# FSPad_sch.net
KiCad netlist of a schematic drawn in EAGLE
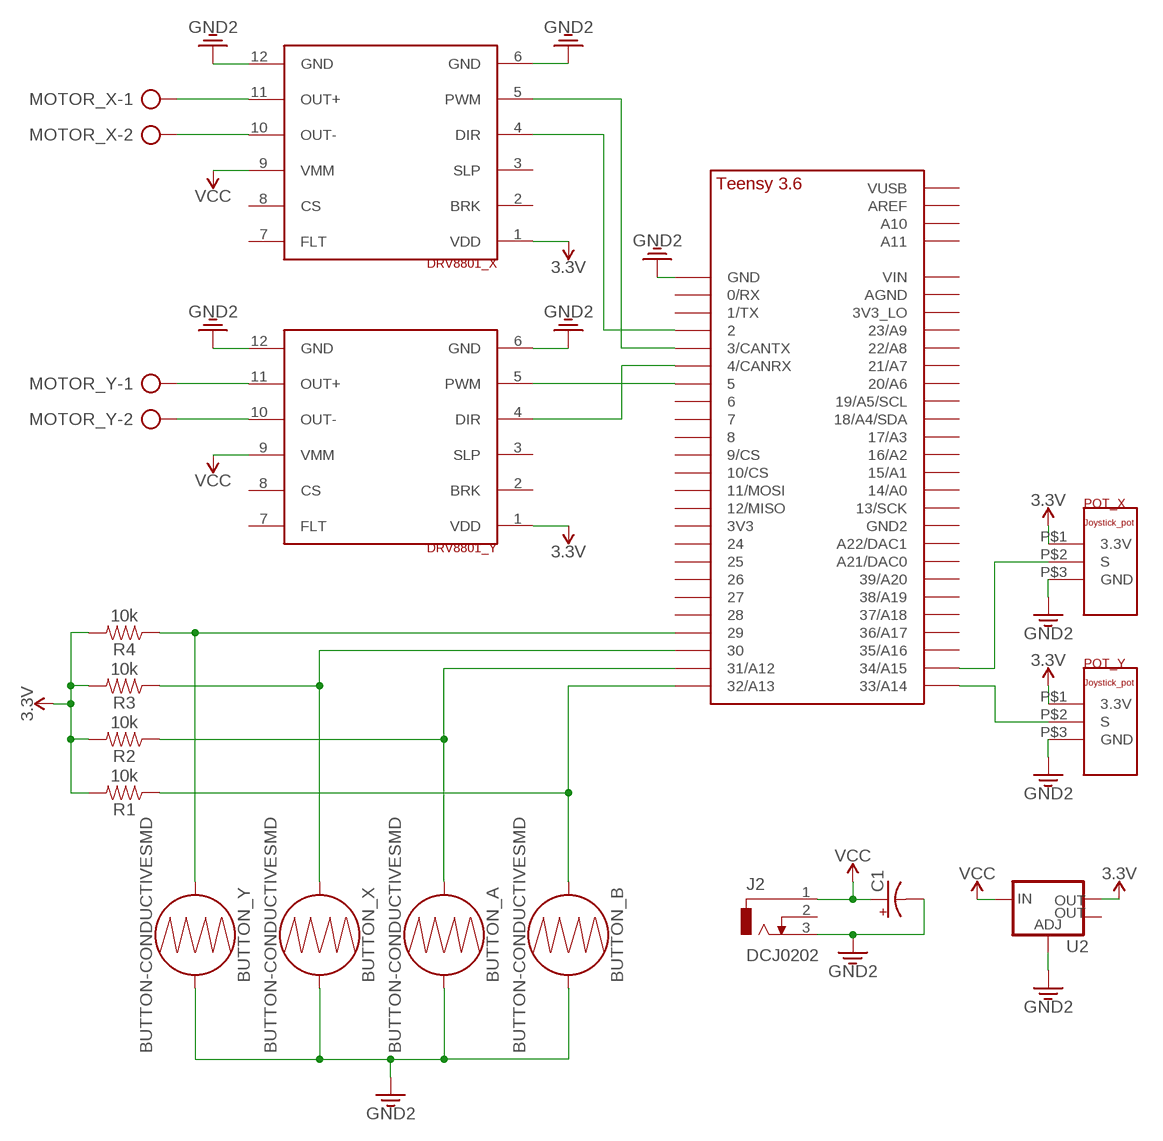
[diagram p0: schematic, sheet 1]

(export (version "E")
  (design (tool "Eeschema 10.0.6"))
  (components
    (comp (ref "BUTTON_A")
      (value "BUTTON-CONDUCTIVESMD")
      (footprint "eagle-import:BUTTON-CONDUCTIVE")
      (libsource (lib "eagle-import") (part "BUTTON-CONDUCTIVESMD"))
    )
    (comp (ref "BUTTON_B")
      (value "BUTTON-CONDUCTIVESMD")
      (footprint "eagle-import:BUTTON-CONDUCTIVE")
      (libsource (lib "eagle-import") (part "BUTTON-CONDUCTIVESMD"))
    )
    (comp (ref "BUTTON_X")
      (value "BUTTON-CONDUCTIVESMD")
      (footprint "eagle-import:BUTTON-CONDUCTIVE")
      (libsource (lib "eagle-import") (part "BUTTON-CONDUCTIVESMD"))
    )
    (comp (ref "BUTTON_Y")
      (value "BUTTON-CONDUCTIVESMD")
      (footprint "eagle-import:BUTTON-CONDUCTIVE")
      (libsource (lib "eagle-import") (part "BUTTON-CONDUCTIVESMD"))
    )
    (comp (ref "C1")
      (value "1mF")
      (footprint "eagle-import:CPOL-RADIAL-5MM-10MM")
      (libsource (lib "eagle-import") (part "1000UF-RADIAL-5MM-25V-20%"))
    )
    (comp (ref "DRV8801_X")
      (value "DRV8801_BREAKOUT_BOARD")
      (footprint "eagle-import:DRV8801_BREAKOUT_BOARD")
      (libsource (lib "eagle-import") (part "DRV8801_BREAKOUT_BOARD"))
    )
    (comp (ref "DRV8801_Y")
      (value "DRV8801_BREAKOUT_BOARD")
      (footprint "eagle-import:DRV8801_BREAKOUT_BOARD")
      (libsource (lib "eagle-import") (part "DRV8801_BREAKOUT_BOARD"))
    )
    (comp (ref "J2")
      (value "DCJ0202")
      (footprint "eagle-import:DCJ0202")
      (libsource (lib "eagle-import") (part "DCJ0202"))
    )
    (comp (ref "MOTOR_X")
      (value "AK300/2")
      (footprint "eagle-import:AK300_2")
      (libsource (lib "eagle-import") (part "AK300/2"))
    )
    (comp (ref "MOTOR_Y")
      (value "AK300/2")
      (footprint "eagle-import:AK300_2")
      (libsource (lib "eagle-import") (part "AK300/2"))
    )
    (comp (ref "POT_X")
      (value "JOYSTICK_POT")
      (footprint "eagle-import:JOYSTICK_POT")
      (libsource (lib "eagle-import") (part "JOYSTICK_POT"))
    )
    (comp (ref "POT_Y")
      (value "JOYSTICK_POT")
      (footprint "eagle-import:JOYSTICK_POT")
      (libsource (lib "eagle-import") (part "JOYSTICK_POT"))
    )
    (comp (ref "R1")
      (value "10k")
      (footprint "eagle-import:AXIAL-0.3")
      (libsource (lib "eagle-import") (part "10KOHM-HORIZ-1/4W-1%"))
    )
    (comp (ref "R2")
      (value "10k")
      (footprint "eagle-import:AXIAL-0.3")
      (libsource (lib "eagle-import") (part "10KOHM-HORIZ-1/4W-1%"))
    )
    (comp (ref "R3")
      (value "10k")
      (footprint "eagle-import:AXIAL-0.3")
      (libsource (lib "eagle-import") (part "10KOHM-HORIZ-1/4W-1%"))
    )
    (comp (ref "R4")
      (value "10k")
      (footprint "eagle-import:AXIAL-0.3")
      (libsource (lib "eagle-import") (part "10KOHM-HORIZ-1/4W-1%"))
    )
    (comp (ref "U$1")
      (value "TEENSY_3.5/3.6_BASIC")
      (footprint "eagle-import:TEENSY_3.5_3.6_BASIC")
      (libsource (lib "eagle-import") (part "TEENSY_3.5/3.6_BASIC"))
    )
    (comp (ref "U2")
      (value "V_REG_LM1117SOT223")
      (footprint "eagle-import:SOT223")
      (libsource (lib "eagle-import") (part "V_REG_LM1117SOT223"))
    )
  )
  (nets
    (net (code "1") (name "3.3V") (class "Default")
      (node (ref "BUTTON_A") (pin "2") (pinfunction "2_2") (pintype "passive"))
      (node (ref "BUTTON_B") (pin "2") (pinfunction "2_2") (pintype "passive"))
      (node (ref "BUTTON_X") (pin "2") (pinfunction "2_2") (pintype "passive"))
      (node (ref "BUTTON_Y") (pin "2") (pinfunction "2_2") (pintype "passive"))
      (node (ref "C1") (pin "-") (pinfunction "-_-") (pintype "passive"))
      (node (ref "DRV8801_X") (pin "1") (pinfunction "VDD_1") (pintype "power_in"))
      (node (ref "DRV8801_X") (pin "12") (pinfunction "GND_12") (pintype "passive"))
      (node (ref "DRV8801_X") (pin "6") (pinfunction "GND_6") (pintype "passive"))
      (node (ref "DRV8801_Y") (pin "1") (pinfunction "VDD_1") (pintype "power_in"))
      (node (ref "DRV8801_Y") (pin "12") (pinfunction "GND_12") (pintype "passive"))
      (node (ref "DRV8801_Y") (pin "6") (pinfunction "GND_6") (pintype "passive"))
      (node (ref "J2") (pin "3") (pinfunction "3_3") (pintype "passive"))
      (node (ref "POT_X") (pin "P$1") (pinfunction "3.3V_P$1") (pintype "power_in"))
      (node (ref "POT_X") (pin "P$3") (pinfunction "GND_P$3") (pintype "passive"))
      (node (ref "POT_Y") (pin "P$1") (pinfunction "3.3V_P$1") (pintype "power_in"))
      (node (ref "POT_Y") (pin "P$3") (pinfunction "GND_P$3") (pintype "passive"))
      (node (ref "R1") (pin "P$2") (pinfunction "2_P$2") (pintype "passive"))
      (node (ref "R2") (pin "P$2") (pinfunction "2_P$2") (pintype "passive"))
      (node (ref "R3") (pin "P$2") (pinfunction "2_P$2") (pintype "passive"))
      (node (ref "R4") (pin "P$2") (pinfunction "2_P$2") (pintype "passive"))
      (node (ref "U$1") (pin "GND") (pinfunction "GND_GND") (pintype "bidirectional"))
      (node (ref "U2") (pin "1") (pinfunction "ADJ_1") (pintype "input"))
      (node (ref "U2") (pin "2") (pinfunction "OUT_2") (pintype "output"))
    )
    (net (code "2") (name "Net-(DRV8801_X-DIR)") (class "Default")
      (node (ref "DRV8801_X") (pin "4") (pinfunction "DIR_4") (pintype "input"))
      (node (ref "U$1") (pin "2") (pinfunction "2_2") (pintype "bidirectional"))
    )
    (net (code "3") (name "Net-(DRV8801_X-OUT+)") (class "Default")
      (node (ref "DRV8801_X") (pin "11") (pinfunction "OUT+_11") (pintype "output"))
      (node (ref "MOTOR_X") (pin "1") (pinfunction "KL_1") (pintype "passive"))
    )
    (net (code "4") (name "Net-(DRV8801_X-OUT-)") (class "Default")
      (node (ref "DRV8801_X") (pin "10") (pinfunction "OUT-_10") (pintype "output"))
      (node (ref "MOTOR_X") (pin "2") (pinfunction "KL_2") (pintype "passive"))
    )
    (net (code "5") (name "Net-(DRV8801_X-PWM)") (class "Default")
      (node (ref "DRV8801_X") (pin "5") (pinfunction "PWM_5") (pintype "input"))
      (node (ref "U$1") (pin "3/CANTX") (pinfunction "3/CANTX_3/CANTX") (pintype "bidirectional"))
    )
    (net (code "6") (name "Net-(DRV8801_Y-DIR)") (class "Default")
      (node (ref "DRV8801_Y") (pin "4") (pinfunction "DIR_4") (pintype "input"))
      (node (ref "U$1") (pin "4/CANRX") (pinfunction "4/CANRX_4/CANRX") (pintype "bidirectional"))
    )
    (net (code "7") (name "Net-(DRV8801_Y-OUT+)") (class "Default")
      (node (ref "DRV8801_Y") (pin "11") (pinfunction "OUT+_11") (pintype "output"))
      (node (ref "MOTOR_Y") (pin "1") (pinfunction "KL_1") (pintype "passive"))
    )
    (net (code "8") (name "Net-(DRV8801_Y-OUT-)") (class "Default")
      (node (ref "DRV8801_Y") (pin "10") (pinfunction "OUT-_10") (pintype "output"))
      (node (ref "MOTOR_Y") (pin "2") (pinfunction "KL_2") (pintype "passive"))
    )
    (net (code "9") (name "Net-(DRV8801_Y-PWM)") (class "Default")
      (node (ref "DRV8801_Y") (pin "5") (pinfunction "PWM_5") (pintype "input"))
      (node (ref "U$1") (pin "5") (pinfunction "5_5") (pintype "bidirectional"))
    )
    (net (code "10") (name "Net-(POT_X-S)") (class "Default")
      (node (ref "POT_X") (pin "P$2") (pinfunction "S_P$2") (pintype "output"))
      (node (ref "U$1") (pin "34/A15") (pinfunction "34/A15_34/A15") (pintype "bidirectional"))
    )
    (net (code "11") (name "Net-(POT_Y-S)") (class "Default")
      (node (ref "POT_Y") (pin "P$2") (pinfunction "S_P$2") (pintype "output"))
      (node (ref "U$1") (pin "33/A14") (pinfunction "33/A14_33/A14") (pintype "bidirectional"))
    )
    (net (code "12") (name "Net-(R1-1)") (class "Default")
      (node (ref "BUTTON_B") (pin "1") (pinfunction "1_1") (pintype "passive"))
      (node (ref "R1") (pin "P$1") (pinfunction "1_P$1") (pintype "passive"))
      (node (ref "U$1") (pin "32/A13") (pinfunction "32/A13_32/A13") (pintype "bidirectional"))
    )
    (net (code "13") (name "Net-(R2-1)") (class "Default")
      (node (ref "BUTTON_A") (pin "1") (pinfunction "1_1") (pintype "passive"))
      (node (ref "R2") (pin "P$1") (pinfunction "1_P$1") (pintype "passive"))
      (node (ref "U$1") (pin "31/A12") (pinfunction "31/A12_31/A12") (pintype "bidirectional"))
    )
    (net (code "14") (name "Net-(R3-1)") (class "Default")
      (node (ref "BUTTON_X") (pin "1") (pinfunction "1_1") (pintype "passive"))
      (node (ref "R3") (pin "P$1") (pinfunction "1_P$1") (pintype "passive"))
      (node (ref "U$1") (pin "30") (pinfunction "30_30") (pintype "bidirectional"))
    )
    (net (code "15") (name "Net-(R4-1)") (class "Default")
      (node (ref "BUTTON_Y") (pin "1") (pinfunction "1_1") (pintype "passive"))
      (node (ref "R4") (pin "P$1") (pinfunction "1_P$1") (pintype "passive"))
      (node (ref "U$1") (pin "29") (pinfunction "29_29") (pintype "bidirectional"))
    )
    (net (code "16") (name "VCC") (class "Default")
      (node (ref "C1") (pin "+") (pinfunction "+_+") (pintype "passive"))
      (node (ref "DRV8801_X") (pin "9") (pinfunction "VMM_9") (pintype "power_in"))
      (node (ref "DRV8801_Y") (pin "9") (pinfunction "VMM_9") (pintype "power_in"))
      (node (ref "J2") (pin "1") (pinfunction "1_1") (pintype "passive"))
      (node (ref "U2") (pin "3") (pinfunction "IN_3") (pintype "input"))
    )
    (net (code "17") (name "unconnected-(DRV8801_X-BRK-Pad2)") (class "Default")
      (node (ref "DRV8801_X") (pin "2") (pinfunction "BRK_2") (pintype "input"))
    )
    (net (code "18") (name "unconnected-(DRV8801_X-CS-Pad8)") (class "Default")
      (node (ref "DRV8801_X") (pin "8") (pinfunction "CS_8") (pintype "output"))
    )
    (net (code "19") (name "unconnected-(DRV8801_X-FLT-Pad7)") (class "Default")
      (node (ref "DRV8801_X") (pin "7") (pinfunction "FLT_7") (pintype "open_collector"))
    )
    (net (code "20") (name "unconnected-(DRV8801_X-SLP-Pad3)") (class "Default")
      (node (ref "DRV8801_X") (pin "3") (pinfunction "SLP_3") (pintype "input"))
    )
    (net (code "21") (name "unconnected-(DRV8801_Y-BRK-Pad2)") (class "Default")
      (node (ref "DRV8801_Y") (pin "2") (pinfunction "BRK_2") (pintype "input"))
    )
    (net (code "22") (name "unconnected-(DRV8801_Y-CS-Pad8)") (class "Default")
      (node (ref "DRV8801_Y") (pin "8") (pinfunction "CS_8") (pintype "output"))
    )
    (net (code "23") (name "unconnected-(DRV8801_Y-FLT-Pad7)") (class "Default")
      (node (ref "DRV8801_Y") (pin "7") (pinfunction "FLT_7") (pintype "open_collector"))
    )
    (net (code "24") (name "unconnected-(DRV8801_Y-SLP-Pad3)") (class "Default")
      (node (ref "DRV8801_Y") (pin "3") (pinfunction "SLP_3") (pintype "input"))
    )
    (net (code "25") (name "unconnected-(J2-Pad2)") (class "Default")
      (node (ref "J2") (pin "2") (pinfunction "2_2") (pintype "passive"))
    )
    (net (code "26") (name "unconnected-(U$1-A21{slash}DAC0-Pad21{slash}DAC0)") (class "Default")
      (node (ref "U$1") (pin "21/DAC0") (pinfunction "A21/DAC0_21/DAC0") (pintype "bidirectional"))
    )
    (net (code "27") (name "unconnected-(U$1-Pad0{slash}RX)") (class "Default")
      (node (ref "U$1") (pin "0/RX") (pinfunction "0/RX_0/RX") (pintype "bidirectional"))
    )
    (net (code "28") (name "unconnected-(U$1-Pad1{slash}TX)") (class "Default")
      (node (ref "U$1") (pin "1/TX") (pinfunction "1/TX_1/TX") (pintype "bidirectional"))
    )
    (net (code "29") (name "unconnected-(U$1-Pad3V3)") (class "Default")
      (node (ref "U$1") (pin "3V3") (pinfunction "3V3_3V3") (pintype "bidirectional"))
    )
    (net (code "30") (name "unconnected-(U$1-Pad3V3_LO)") (class "Default")
      (node (ref "U$1") (pin "3V3_LO") (pinfunction "3V3_LO_3V3_LO") (pintype "bidirectional"))
    )
    (net (code "31") (name "unconnected-(U$1-Pad6)") (class "Default")
      (node (ref "U$1") (pin "6") (pinfunction "6_6") (pintype "bidirectional"))
    )
    (net (code "32") (name "unconnected-(U$1-Pad7)") (class "Default")
      (node (ref "U$1") (pin "7") (pinfunction "7_7") (pintype "bidirectional"))
    )
    (net (code "33") (name "unconnected-(U$1-Pad8)") (class "Default")
      (node (ref "U$1") (pin "8") (pinfunction "8_8") (pintype "bidirectional"))
    )
    (net (code "34") (name "unconnected-(U$1-Pad9{slash}CS)") (class "Default")
      (node (ref "U$1") (pin "9/CS") (pinfunction "9/CS_9/CS") (pintype "bidirectional"))
    )
    (net (code "35") (name "unconnected-(U$1-Pad10{slash}CS)") (class "Default")
      (node (ref "U$1") (pin "10/CS") (pinfunction "10/CS_10/CS") (pintype "bidirectional"))
    )
    (net (code "36") (name "unconnected-(U$1-Pad11{slash}MOSI)") (class "Default")
      (node (ref "U$1") (pin "11/MOSI") (pinfunction "11/MOSI_11/MOSI") (pintype "bidirectional"))
    )
    (net (code "37") (name "unconnected-(U$1-Pad12{slash}MISO)") (class "Default")
      (node (ref "U$1") (pin "12/MISO") (pinfunction "12/MISO_12/MISO") (pintype "bidirectional"))
    )
    (net (code "38") (name "unconnected-(U$1-Pad13{slash}SCK)") (class "Default")
      (node (ref "U$1") (pin "13/SCK") (pinfunction "13/SCK_13/SCK") (pintype "bidirectional"))
    )
    (net (code "39") (name "unconnected-(U$1-Pad14{slash}A0)") (class "Default")
      (node (ref "U$1") (pin "14/A0") (pinfunction "14/A0_14/A0") (pintype "bidirectional"))
    )
    (net (code "40") (name "unconnected-(U$1-Pad15{slash}A1)") (class "Default")
      (node (ref "U$1") (pin "15/A1") (pinfunction "15/A1_15/A1") (pintype "bidirectional"))
    )
    (net (code "41") (name "unconnected-(U$1-Pad16{slash}A2)") (class "Default")
      (node (ref "U$1") (pin "16/A2") (pinfunction "16/A2_16/A2") (pintype "bidirectional"))
    )
    (net (code "42") (name "unconnected-(U$1-Pad17{slash}A3)") (class "Default")
      (node (ref "U$1") (pin "17/A3") (pinfunction "17/A3_17/A3") (pintype "bidirectional"))
    )
    (net (code "43") (name "unconnected-(U$1-Pad18{slash}A4{slash}SDA)") (class "Default")
      (node (ref "U$1") (pin "18/A4/SDA") (pinfunction "18/A4/SDA_18/A4/SDA") (pintype "bidirectional"))
    )
    (net (code "44") (name "unconnected-(U$1-Pad19{slash}A5{slash}SCL)") (class "Default")
      (node (ref "U$1") (pin "19/A5/SCL") (pinfunction "19/A5/SCL_19/A5/SCL") (pintype "bidirectional"))
    )
    (net (code "45") (name "unconnected-(U$1-Pad20{slash}A6)") (class "Default")
      (node (ref "U$1") (pin "20/A6") (pinfunction "20/A6_20/A6") (pintype "bidirectional"))
    )
    (net (code "46") (name "unconnected-(U$1-Pad21{slash}A7)") (class "Default")
      (node (ref "U$1") (pin "21/A7") (pinfunction "21/A7_21/A7") (pintype "bidirectional"))
    )
    (net (code "47") (name "unconnected-(U$1-Pad22{slash}A8)") (class "Default")
      (node (ref "U$1") (pin "22/A8") (pinfunction "22/A8_22/A8") (pintype "bidirectional"))
    )
    (net (code "48") (name "unconnected-(U$1-Pad23{slash}A9)") (class "Default")
      (node (ref "U$1") (pin "23/A9") (pinfunction "23/A9_23/A9") (pintype "bidirectional"))
    )
    (net (code "49") (name "unconnected-(U$1-Pad24)") (class "Default")
      (node (ref "U$1") (pin "24") (pinfunction "24_24") (pintype "bidirectional"))
    )
    (net (code "50") (name "unconnected-(U$1-Pad25)") (class "Default")
      (node (ref "U$1") (pin "25") (pinfunction "25_25") (pintype "bidirectional"))
    )
    (net (code "51") (name "unconnected-(U$1-Pad26)") (class "Default")
      (node (ref "U$1") (pin "26") (pinfunction "26_26") (pintype "bidirectional"))
    )
    (net (code "52") (name "unconnected-(U$1-Pad27)") (class "Default")
      (node (ref "U$1") (pin "27") (pinfunction "27_27") (pintype "bidirectional"))
    )
    (net (code "53") (name "unconnected-(U$1-Pad28)") (class "Default")
      (node (ref "U$1") (pin "28") (pinfunction "28_28") (pintype "bidirectional"))
    )
    (net (code "54") (name "unconnected-(U$1-Pad35{slash}A16)") (class "Default")
      (node (ref "U$1") (pin "35/A16") (pinfunction "35/A16_35/A16") (pintype "bidirectional"))
    )
    (net (code "55") (name "unconnected-(U$1-Pad36{slash}A17)") (class "Default")
      (node (ref "U$1") (pin "36/A17") (pinfunction "36/A17_36/A17") (pintype "bidirectional"))
    )
    (net (code "56") (name "unconnected-(U$1-Pad37{slash}A18)") (class "Default")
      (node (ref "U$1") (pin "37/A18") (pinfunction "37/A18_37/A18") (pintype "bidirectional"))
    )
    (net (code "57") (name "unconnected-(U$1-Pad38{slash}A19)") (class "Default")
      (node (ref "U$1") (pin "38/A19") (pinfunction "38/A19_38/A19") (pintype "bidirectional"))
    )
    (net (code "58") (name "unconnected-(U$1-Pad39{slash}A20)") (class "Default")
      (node (ref "U$1") (pin "39/A20") (pinfunction "39/A20_39/A20") (pintype "bidirectional"))
    )
    (net (code "59") (name "unconnected-(U$1-PadA10)") (class "Default")
      (node (ref "U$1") (pin "A10") (pinfunction "A10_A10") (pintype "bidirectional"))
    )
    (net (code "60") (name "unconnected-(U$1-PadA11)") (class "Default")
      (node (ref "U$1") (pin "A11") (pinfunction "A11_A11") (pintype "bidirectional"))
    )
    (net (code "61") (name "unconnected-(U$1-PadA22{slash}DAC1)") (class "Default")
      (node (ref "U$1") (pin "A22/DAC1") (pinfunction "A22/DAC1_A22/DAC1") (pintype "bidirectional"))
    )
    (net (code "62") (name "unconnected-(U$1-PadAGND)") (class "Default")
      (node (ref "U$1") (pin "AGND") (pinfunction "AGND_AGND") (pintype "bidirectional"))
    )
    (net (code "63") (name "unconnected-(U$1-PadAREF)") (class "Default")
      (node (ref "U$1") (pin "AREF") (pinfunction "AREF_AREF") (pintype "bidirectional"))
    )
    (net (code "64") (name "unconnected-(U$1-PadGND2)") (class "Default")
      (node (ref "U$1") (pin "GND2") (pinfunction "GND2_GND2") (pintype "bidirectional"))
    )
    (net (code "65") (name "unconnected-(U$1-PadVIN)") (class "Default")
      (node (ref "U$1") (pin "VIN") (pinfunction "VIN_VIN") (pintype "bidirectional"))
    )
    (net (code "66") (name "unconnected-(U$1-PadVUSB)") (class "Default")
      (node (ref "U$1") (pin "VUSB") (pinfunction "VUSB_VUSB") (pintype "bidirectional"))
    )
    (net (code "67") (name "unconnected-(U2-OUT-Pad4)") (class "Default")
      (node (ref "U2") (pin "4") (pinfunction "OUT_4") (pintype "output"))
    )
  )
)
